# Page05_DDR4L_eMMC.net
KiCad netlist of a schematic drawn in Altium Designer
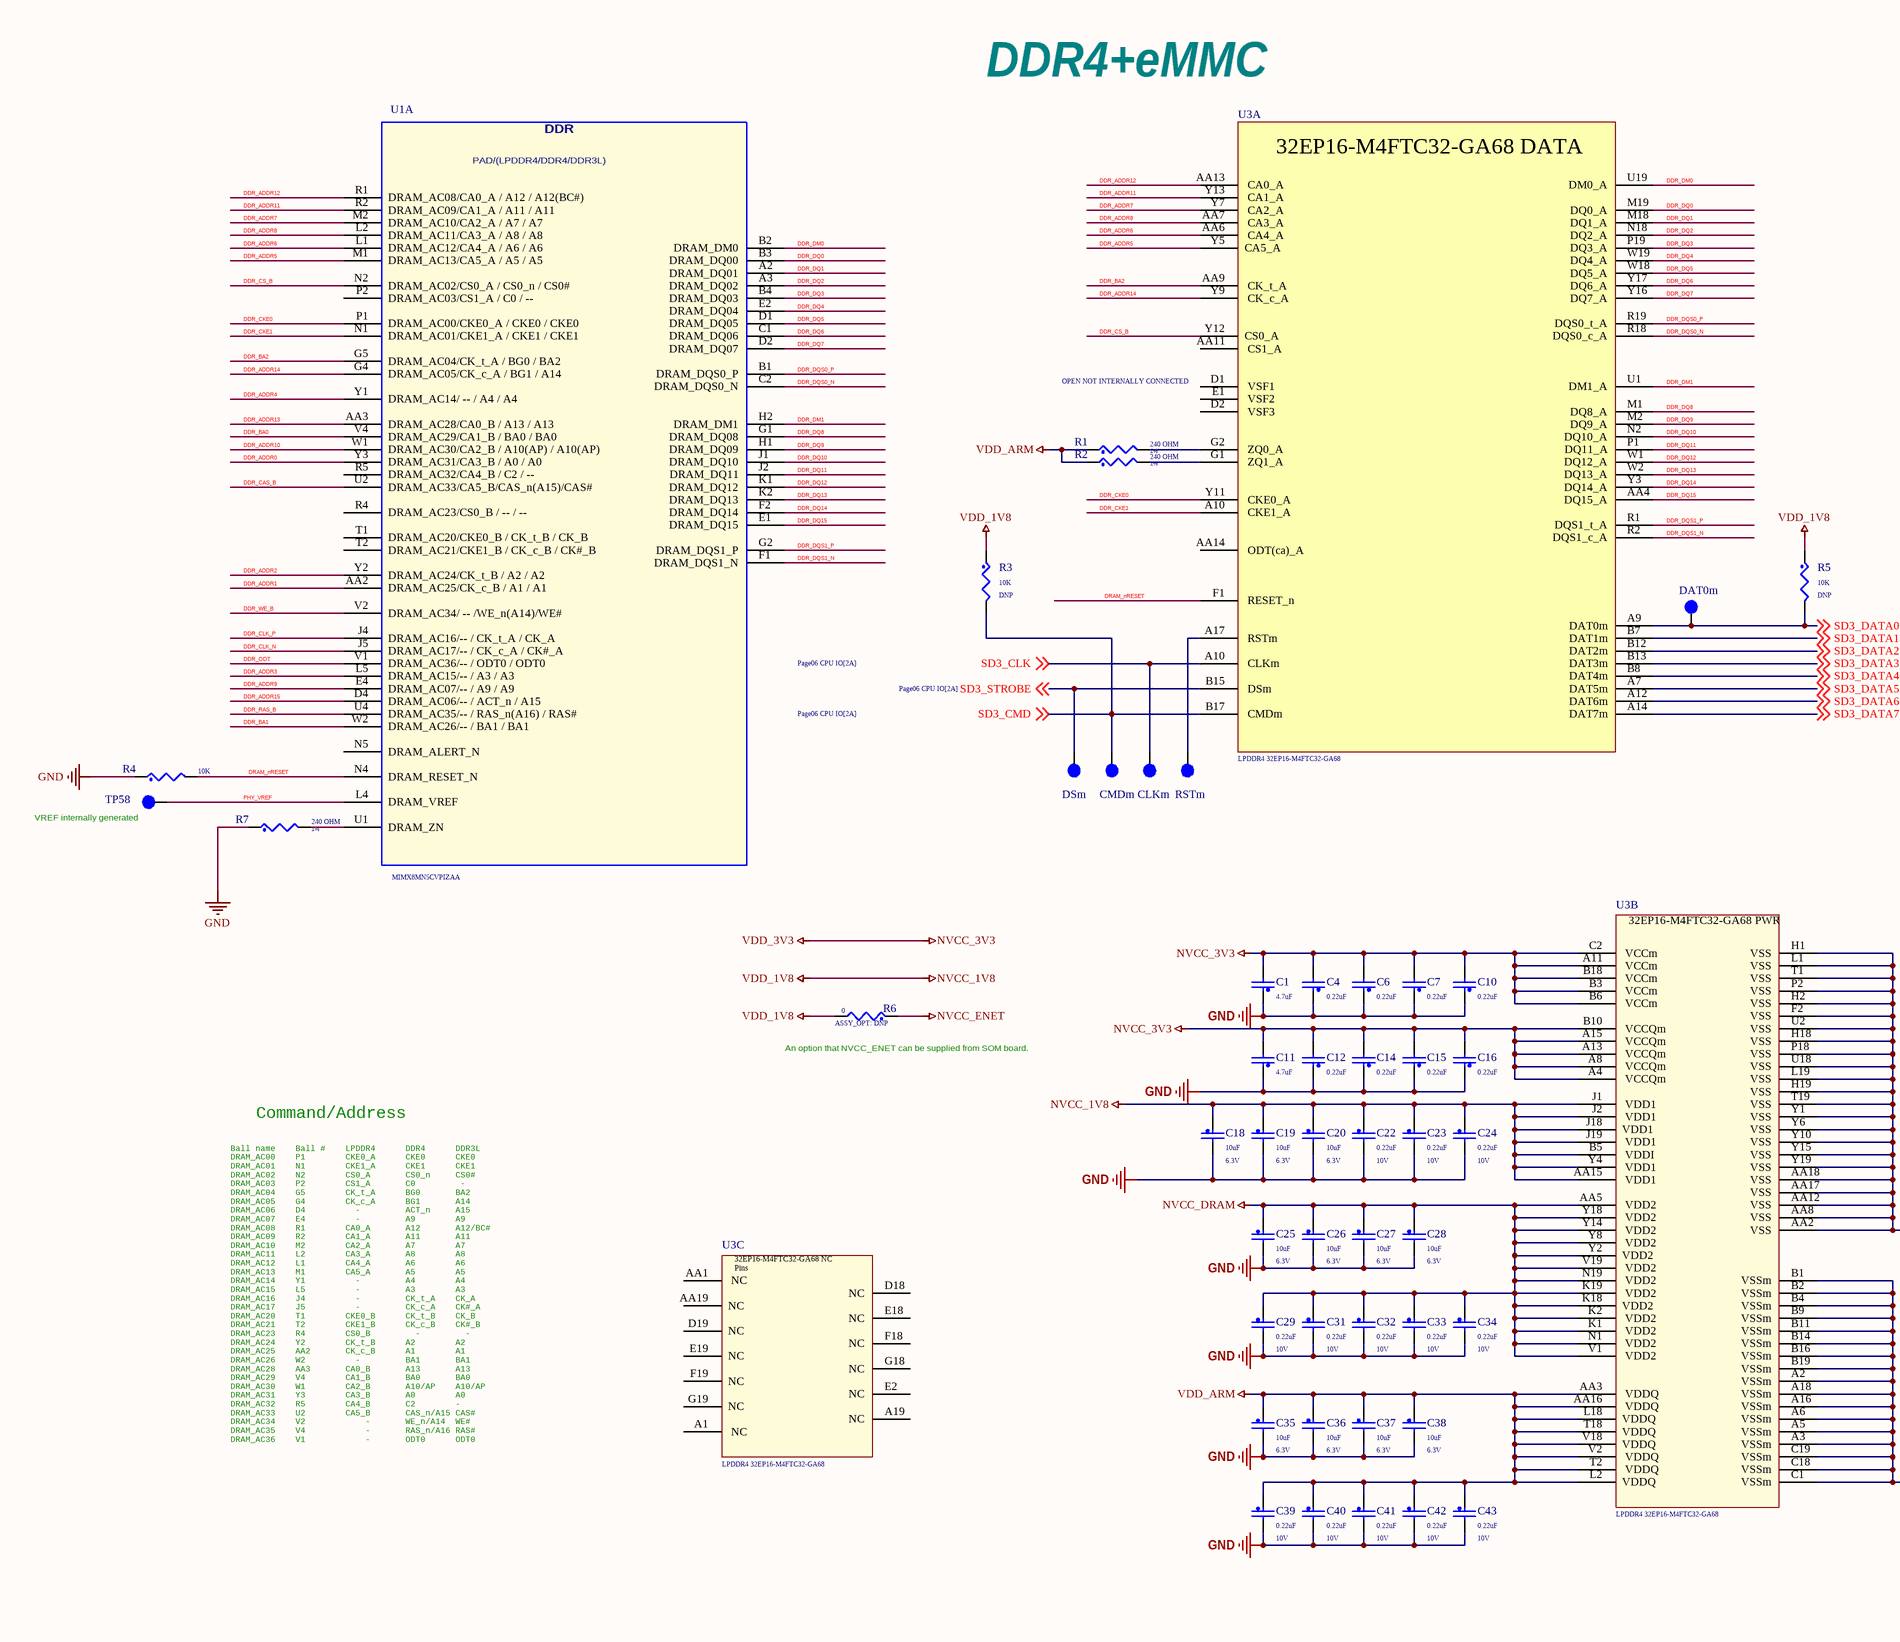
[diagram p0: Page05 DDR4L+eMMC.SchDoc, left]
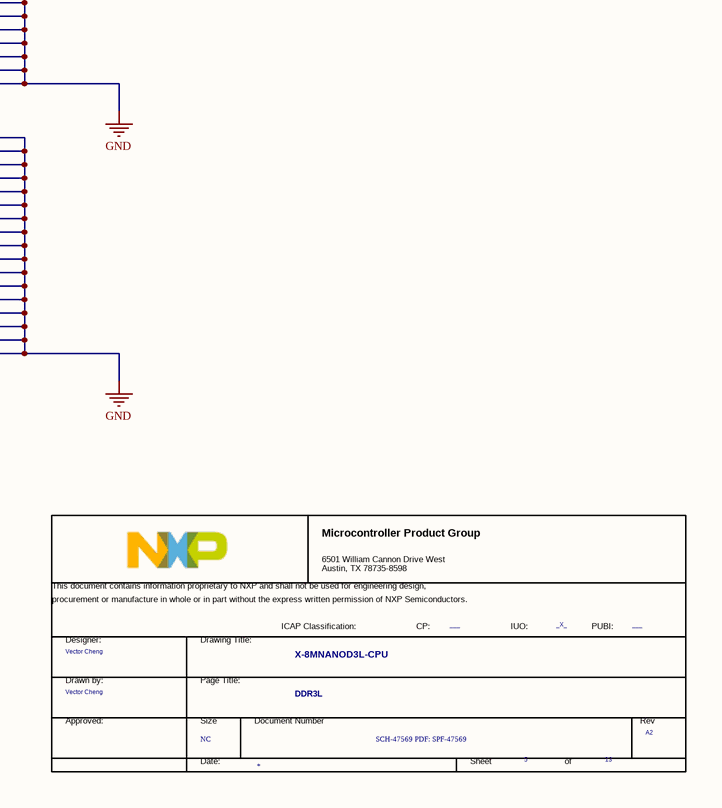
[diagram p1: Page05 DDR4L+eMMC.SchDoc, right]

(export (version "E")
  (design (tool "Eeschema 10.0.6"))
  (components
    (comp (ref "C1") (value "4.7uF") (footprint "0402_CC - C") (libsource (lib "AA_iMX8_M_") (part "CAP_NP")))
    (comp (ref "C4")
      (value "0.22uF")
      (footprint "0201_CC - C")
      (libsource (lib "AA_iMX8_M_") (part "CAP_NP"))
    )
    (comp (ref "C6")
      (value "0.22uF")
      (footprint "0201_CC - C")
      (libsource (lib "AA_iMX8_M_") (part "CAP_NP"))
    )
    (comp (ref "C7")
      (value "0.22uF")
      (footprint "0201_CC - C")
      (libsource (lib "AA_iMX8_M_") (part "CAP_NP"))
    )
    (comp (ref "C10")
      (value "0.22uF")
      (footprint "0201_CC - C")
      (libsource (lib "AA_iMX8_M_") (part "CAP_NP"))
    )
    (comp (ref "C11")
      (value "4.7uF")
      (footprint "0402_CC - C")
      (libsource (lib "AA_iMX8_M_") (part "CAP_NP"))
    )
    (comp (ref "C12")
      (value "0.22uF")
      (footprint "0201_CC - C")
      (libsource (lib "AA_iMX8_M_") (part "CAP_NP"))
    )
    (comp (ref "C14")
      (value "0.22uF")
      (footprint "0201_CC - C")
      (libsource (lib "AA_iMX8_M_") (part "CAP_NP"))
    )
    (comp (ref "C15")
      (value "0.22uF")
      (footprint "0201_CC - C")
      (libsource (lib "AA_iMX8_M_") (part "CAP_NP"))
    )
    (comp (ref "C16")
      (value "0.22uF")
      (footprint "0201_CC - C")
      (libsource (lib "AA_iMX8_M_") (part "CAP_NP"))
    )
    (comp (ref "C18")
      (value "10uF")
      (footprint "0402_CC - C")
      (fields (field (name "VOLTAGE") "6.3V"))
      (libsource (lib "AA_iMX8_M_") (part "CAP_NP"))
    )
    (comp (ref "C19")
      (value "10uF")
      (footprint "0402_CC - C")
      (fields (field (name "VOLTAGE") "6.3V"))
      (libsource (lib "AA_iMX8_M_") (part "CAP_NP"))
    )
    (comp (ref "C20")
      (value "10uF")
      (footprint "0402_CC - C")
      (fields (field (name "VOLTAGE") "6.3V"))
      (libsource (lib "AA_iMX8_M_") (part "CAP_NP"))
    )
    (comp (ref "C22")
      (value "0.22uF")
      (footprint "0201_CC - C")
      (fields (field (name "VOLTAGE") "10V"))
      (libsource (lib "AA_iMX8_M_") (part "CAP_NP"))
    )
    (comp (ref "C23")
      (value "0.22uF")
      (footprint "0201_CC - C")
      (fields (field (name "VOLTAGE") "10V"))
      (libsource (lib "AA_iMX8_M_") (part "CAP_NP"))
    )
    (comp (ref "C24")
      (value "0.22uF")
      (footprint "0201_CC - C")
      (fields (field (name "VOLTAGE") "10V"))
      (libsource (lib "AA_iMX8_M_") (part "CAP_NP"))
    )
    (comp (ref "C25")
      (value "10uF")
      (footprint "0402_CC - C")
      (fields (field (name "VOLTAGE") "6.3V"))
      (libsource (lib "AA_iMX8_M_") (part "CAP_NP"))
    )
    (comp (ref "C26")
      (value "10uF")
      (footprint "0402_CC - C")
      (fields (field (name "VOLTAGE") "6.3V"))
      (libsource (lib "AA_iMX8_M_") (part "CAP_NP"))
    )
    (comp (ref "C27")
      (value "10uF")
      (footprint "0402_CC - C")
      (fields (field (name "VOLTAGE") "6.3V"))
      (libsource (lib "AA_iMX8_M_") (part "CAP_NP"))
    )
    (comp (ref "C28")
      (value "10uF")
      (footprint "0402_CC - C")
      (fields (field (name "VOLTAGE") "6.3V"))
      (libsource (lib "AA_iMX8_M_") (part "CAP_NP"))
    )
    (comp (ref "C29")
      (value "0.22uF")
      (footprint "0201_CC - C")
      (fields (field (name "VOLTAGE") "10V"))
      (libsource (lib "AA_iMX8_M_") (part "CAP_NP"))
    )
    (comp (ref "C31")
      (value "0.22uF")
      (footprint "0201_CC - C")
      (fields (field (name "VOLTAGE") "10V"))
      (libsource (lib "AA_iMX8_M_") (part "CAP_NP"))
    )
    (comp (ref "C32")
      (value "0.22uF")
      (footprint "0201_CC - C")
      (fields (field (name "VOLTAGE") "10V"))
      (libsource (lib "AA_iMX8_M_") (part "CAP_NP"))
    )
    (comp (ref "C33")
      (value "0.22uF")
      (footprint "0201_CC - C")
      (fields (field (name "VOLTAGE") "10V"))
      (libsource (lib "AA_iMX8_M_") (part "CAP_NP"))
    )
    (comp (ref "C34")
      (value "0.22uF")
      (footprint "0201_CC - C")
      (fields (field (name "VOLTAGE") "10V"))
      (libsource (lib "AA_iMX8_M_") (part "CAP_NP"))
    )
    (comp (ref "C35")
      (value "10uF")
      (footprint "0402_CC - C")
      (fields (field (name "VOLTAGE") "6.3V"))
      (libsource (lib "AA_iMX8_M_") (part "CAP_NP"))
    )
    (comp (ref "C36")
      (value "10uF")
      (footprint "0402_CC - C")
      (fields (field (name "VOLTAGE") "6.3V"))
      (libsource (lib "AA_iMX8_M_") (part "CAP_NP"))
    )
    (comp (ref "C37")
      (value "10uF")
      (footprint "0402_CC - C")
      (fields (field (name "VOLTAGE") "6.3V"))
      (libsource (lib "AA_iMX8_M_") (part "CAP_NP"))
    )
    (comp (ref "C38")
      (value "10uF")
      (footprint "0402_CC - C")
      (fields (field (name "VOLTAGE") "6.3V"))
      (libsource (lib "AA_iMX8_M_") (part "CAP_NP"))
    )
    (comp (ref "C39")
      (value "0.22uF")
      (footprint "0201_CC - C")
      (fields (field (name "VOLTAGE") "10V"))
      (libsource (lib "AA_iMX8_M_") (part "CAP_NP"))
    )
    (comp (ref "C40")
      (value "0.22uF")
      (footprint "0201_CC - C")
      (fields (field (name "VOLTAGE") "10V"))
      (libsource (lib "AA_iMX8_M_") (part "CAP_NP"))
    )
    (comp (ref "C41")
      (value "0.22uF")
      (footprint "0201_CC - C")
      (fields (field (name "VOLTAGE") "10V"))
      (libsource (lib "AA_iMX8_M_") (part "CAP_NP"))
    )
    (comp (ref "C42")
      (value "0.22uF")
      (footprint "0201_CC - C")
      (fields (field (name "VOLTAGE") "10V"))
      (libsource (lib "AA_iMX8_M_") (part "CAP_NP"))
    )
    (comp (ref "C43")
      (value "0.22uF")
      (footprint "0201_CC - C")
      (fields (field (name "VOLTAGE") "10V"))
      (libsource (lib "AA_iMX8_M_") (part "CAP_NP"))
    )
    (comp (ref "CLKm")
      (value "tpad_020")
      (footprint "Test Pin")
      (description "TEST POINT PAD 0.5MM DIA SMT, NO PART TO ORDER")
      (libsource (lib "*") (part "TESTLOOP"))
    )
    (comp (ref "CMDm")
      (value "TPAD_015")
      (footprint "Test Pin")
      (description "TEST POINT PAD 15MIL DIA SMT, NO PART TO ORDER")
      (libsource (lib "*") (part "TESTLOOP"))
    )
    (comp (ref "DAT0m")
      (value "tpad_020")
      (footprint "Test Pin")
      (description "TEST POINT PAD 0.5MM DIA SMT, NO PART TO ORDER")
      (libsource (lib "*") (part "TESTLOOP"))
    )
    (comp (ref "DSm")
      (value "TPAD_015")
      (footprint "Test Pin")
      (description "TEST POINT PAD 15MIL DIA SMT, NO PART TO ORDER")
      (libsource (lib "*") (part "TESTLOOP"))
    )
    (comp (ref "R1")
      (value "240 OHM")
      (footprint "0201_RES")
      (description "RES MF 240 OHM 1/20W 1% 0201")
      (fields (field (name "VOLTAGE") "25V") (field (name "TOLERANCE") "1%"))
      (libsource (lib "*") (part "RES"))
    )
    (comp (ref "R2")
      (value "240 OHM")
      (footprint "0201_RES")
      (description "RES MF 240 OHM 1/20W 1% 0201")
      (fields (field (name "VOLTAGE") "25V") (field (name "TOLERANCE") "1%"))
      (libsource (lib "*") (part "RES"))
    )
    (comp (ref "R3")
      (value "10K")
      (footprint "0201_RES")
      (description "RES MF 10K 1/20W 5% 0201")
      (fields (field (name "ASSY_OPT") "DNP") (field (name "TOLERANCE") "5%"))
      (libsource (lib "*") (part "RES"))
    )
    (comp (ref "R4")
      (value "10K")
      (footprint "0201_RES")
      (description "RES MF 10K 1/20W 5% 0201")
      (fields (field (name "TOLERANCE") "5%"))
      (libsource (lib "*") (part "RES"))
    )
    (comp (ref "R5")
      (value "10K")
      (footprint "0201_RES")
      (description "RES MF 10K 1/20W 5% 0201")
      (fields (field (name "ASSY_OPT") "DNP") (field (name "TOLERANCE") "5%"))
      (libsource (lib "*") (part "RES"))
    )
    (comp (ref "R6")
      (value "0")
      (footprint "0402_CC_RES")
      (description "RES MF ZERO OHM 1/16W 5% 0402")
      (fields
        (field (name "ASSY_OPT") "DNP")
        (field (name "TOLERANCE") "5%")
        (field (name "VOLTAGE") "1/16W")
      )
      (libsource (lib "*") (part "RES"))
    )
    (comp (ref "R7")
      (value "240 OHM")
      (footprint "0201_RES")
      (description "RES MF 240 OHM 1/20W 1% 0201")
      (fields (field (name "VOLTAGE") "25V") (field (name "TOLERANCE") "1%"))
      (libsource (lib "*") (part "RES"))
    )
    (comp (ref "RSTm")
      (value "tpad_020")
      (footprint "Test Pin")
      (description "TEST POINT PAD 0.5MM DIA SMT, NO PART TO ORDER")
      (libsource (lib "*") (part "TESTLOOP"))
    )
    (comp (ref "TP58")
      (value "tpad_020")
      (footprint "Test Pin")
      (description "TEST POINT PAD 0.5MM DIA SMT, NO PART TO ORDER")
      (libsource (lib "*") (part "TESTLOOP"))
    )
    (comp (ref "U1")
      (value "MIMX8MN5CVPIZAA")
      (footprint "BGA306C50P21X21_1100X1100X101")
      (description "IC CPU QUAD CORTEX A53+M7 1.4GHZ -- BGA306")
      (libsource (lib "*") (part "MIMX8MN"))
    )
    (comp (ref "U3")
      (value "LPDDR4 32EP16-M4FTC32-GA68")
      (footprint "FBGA144C40P19X21_800X950X80")
      (libsource (lib "Altium starter project NANO") (part "LPDDR4 32EP16-M4FTC32-GA68"))
    )
  )
  (nets
    (net (code "1") (name "/DDR_ADDR0") (class "Default")
      (node (ref "U1") (pin "Y3") (pinfunction "DRAM_AC31/CA3_B_/_A0_/_A0_Y3") (pintype "passive"))
    )
    (net (code "2") (name "/DDR_ADDR1") (class "Default")
      (node (ref "U1") (pin "AA2") (pinfunction "DRAM_AC25/CK_c_B_/_A1_/_A1_AA2") (pintype "passive"))
    )
    (net (code "3") (name "/DDR_ADDR2") (class "Default")
      (node (ref "U1") (pin "Y2") (pinfunction "DRAM_AC24/CK_t_B_/_A2_/_A2_Y2") (pintype "passive"))
    )
    (net (code "4") (name "/DDR_ADDR3") (class "Default")
      (node (ref "U1") (pin "L5") (pinfunction "DRAM_AC15/--_/_A3_/_A3_L5") (pintype "passive"))
    )
    (net (code "5") (name "/DDR_ADDR4") (class "Default")
      (node (ref "U1") (pin "Y1") (pinfunction "DRAM_AC14/_--_/_A4_/_A4_Y1") (pintype "passive"))
    )
    (net (code "6") (name "/DDR_ADDR5") (class "Default")
      (node (ref "U1") (pin "M1") (pinfunction "DRAM_AC13/CA5_A_/_A5_/_A5_M1") (pintype "passive"))
      (node (ref "U3") (pin "Y5") (pinfunction "CA5_A_Y5") (pintype "passive"))
    )
    (net (code "7") (name "/DDR_ADDR6") (class "Default")
      (node (ref "U1") (pin "L1") (pinfunction "DRAM_AC12/CA4_A_/_A6_/_A6_L1") (pintype "passive"))
      (node (ref "U3") (pin "AA6") (pinfunction "_CA4_A_AA6") (pintype "passive"))
    )
    (net (code "8") (name "/DDR_ADDR7") (class "Default")
      (node (ref "U1") (pin "M2") (pinfunction "DRAM_AC10/CA2_A_/_A7_/_A7_M2") (pintype "passive"))
      (node (ref "U3") (pin "Y7") (pinfunction "_CA2_A_Y7") (pintype "passive"))
    )
    (net (code "9") (name "/DDR_ADDR8") (class "Default")
      (node (ref "U1") (pin "L2") (pinfunction "DRAM_AC11/CA3_A_/_A8_/_A8_L2") (pintype "passive"))
      (node (ref "U3") (pin "AA7") (pinfunction "_CA3_A_AA7") (pintype "passive"))
    )
    (net (code "10") (name "/DDR_ADDR9") (class "Default")
      (node (ref "U1") (pin "E4") (pinfunction "DRAM_AC07/--_/_A9_/_A9_E4") (pintype "passive"))
    )
    (net (code "11") (name "/DDR_ADDR10") (class "Default")
      (node (ref "U1") (pin "W1") (pinfunction "DRAM_AC30/CA2_B_/_A10(AP)_/_A10(AP)_W1") (pintype "passive"))
    )
    (net (code "12") (name "/DDR_ADDR11") (class "Default")
      (node (ref "U1") (pin "R2") (pinfunction "DRAM_AC09/CA1_A_/_A11_/_A11_R2") (pintype "passive"))
      (node (ref "U3") (pin "Y13") (pinfunction "_CA1_A_Y13") (pintype "passive"))
    )
    (net (code "13") (name "/DDR_ADDR12") (class "Default")
      (node (ref "U1") (pin "R1") (pinfunction "DRAM_AC08/CA0_A_/_A12_/_A12(BC#)_R1") (pintype "passive"))
      (node (ref "U3") (pin "AA13") (pinfunction "_CA0_A_AA13") (pintype "passive"))
    )
    (net (code "14") (name "/DDR_ADDR13") (class "Default")
      (node (ref "U1") (pin "AA3") (pinfunction "DRAM_AC28/CA0_B_/_A13_/_A13_AA3") (pintype "passive"))
    )
    (net (code "15") (name "/DDR_ADDR14") (class "Default")
      (node (ref "U1") (pin "G4") (pinfunction "DRAM_AC05/CK_c_A_/_BG1_/_A14_G4") (pintype "passive"))
      (node (ref "U3") (pin "Y9") (pinfunction "_CK_c_A_Y9") (pintype "passive"))
    )
    (net (code "16") (name "/DDR_ADDR15") (class "Default")
      (node (ref "U1") (pin "D4") (pinfunction "DRAM_AC06/--_/_ACT_n_/_A15_D4") (pintype "passive"))
    )
    (net (code "17") (name "/DDR_BA0") (class "Default")
      (node (ref "U1") (pin "V4") (pinfunction "DRAM_AC29/CA1_B_/_BA0_/_BA0_V4") (pintype "passive"))
    )
    (net (code "18") (name "/DDR_BA1") (class "Default")
      (node (ref "U1") (pin "W2") (pinfunction "DRAM_AC26/--_/_BA1_/_BA1_W2") (pintype "passive"))
    )
    (net (code "19") (name "/DDR_BA2") (class "Default")
      (node (ref "U1") (pin "G5") (pinfunction "DRAM_AC04/CK_t_A_/_BG0_/_BA2_G5") (pintype "passive"))
      (node (ref "U3") (pin "AA9") (pinfunction "_CK_t_A_AA9") (pintype "passive"))
    )
    (net (code "20") (name "/DDR_CAS_B") (class "Default")
      (node (ref "U1") (pin "U2") (pinfunction "DRAM_AC33/CA5_B/CAS_n(A15)/CAS#_U2") (pintype "passive"))
    )
    (net (code "21") (name "/DDR_CKE0") (class "Default")
      (node (ref "U1") (pin "P1") (pinfunction "DRAM_AC00/CKE0_A_/_CKE0_/_CKE0_P1") (pintype "passive"))
      (node (ref "U3") (pin "Y11") (pinfunction "_CKE0_A_Y11") (pintype "passive"))
    )
    (net (code "22") (name "/DDR_CKE1") (class "Default")
      (node (ref "U1") (pin "N1") (pinfunction "DRAM_AC01/CKE1_A_/_CKE1_/_CKE1_N1") (pintype "passive"))
      (node (ref "U3") (pin "A10") (pinfunction "_CKE1_A_A10") (pintype "passive"))
    )
    (net (code "23") (name "/DDR_CLK_N") (class "Default")
      (node (ref "U1") (pin "J5") (pinfunction "DRAM_AC17/--_/_CK_c_A_/_CK#_A_J5") (pintype "passive"))
    )
    (net (code "24") (name "/DDR_CLK_P") (class "Default")
      (node (ref "U1") (pin "J4") (pinfunction "DRAM_AC16/--_/_CK_t_A_/_CK_A_J4") (pintype "passive"))
    )
    (net (code "25") (name "/DDR_CS_B") (class "Default")
      (node (ref "U1") (pin "N2") (pinfunction "DRAM_AC02/CS0_A_/_CS0_n_/_CS0#_N2") (pintype "passive"))
      (node (ref "U3") (pin "Y12") (pinfunction "CS0_A_Y12") (pintype "passive"))
    )
    (net (code "26") (name "/DDR_DM0") (class "Default")
      (node (ref "U1") (pin "B2") (pinfunction "DRAM_DM0_B2") (pintype "passive"))
      (node (ref "U3") (pin "U19") (pinfunction "_DM0_A_U19") (pintype "passive"))
    )
    (net (code "27") (name "/DDR_DM1") (class "Default")
      (node (ref "U1") (pin "H2") (pinfunction "DRAM_DM1_H2") (pintype "passive"))
      (node (ref "U3") (pin "U1") (pinfunction "_DM1_A_U1") (pintype "passive"))
    )
    (net (code "28") (name "/DDR_DQ0") (class "Default")
      (node (ref "U1") (pin "B3") (pinfunction "DRAM_DQ00_B3") (pintype "passive"))
      (node (ref "U3") (pin "M19") (pinfunction "_DQ0_A_M19") (pintype "passive"))
    )
    (net (code "29") (name "/DDR_DQ1") (class "Default")
      (node (ref "U1") (pin "A2") (pinfunction "DRAM_DQ01_A2") (pintype "passive"))
      (node (ref "U3") (pin "M18") (pinfunction "DQ1_A_M18") (pintype "passive"))
    )
    (net (code "30") (name "/DDR_DQ2") (class "Default")
      (node (ref "U1") (pin "A3") (pinfunction "DRAM_DQ02_A3") (pintype "passive"))
      (node (ref "U3") (pin "N18") (pinfunction "DQ2_A_N18") (pintype "passive"))
    )
    (net (code "31") (name "/DDR_DQ3") (class "Default")
      (node (ref "U1") (pin "B4") (pinfunction "DRAM_DQ03_B4") (pintype "passive"))
      (node (ref "U3") (pin "P19") (pinfunction "DQ3_A_P19") (pintype "passive"))
    )
    (net (code "32") (name "/DDR_DQ4") (class "Default")
      (node (ref "U1") (pin "E2") (pinfunction "DRAM_DQ04_E2") (pintype "passive"))
      (node (ref "U3") (pin "W19") (pinfunction "_DQ4_A_W19") (pintype "passive"))
    )
    (net (code "33") (name "/DDR_DQ5") (class "Default")
      (node (ref "U1") (pin "D1") (pinfunction "DRAM_DQ05_D1") (pintype "passive"))
      (node (ref "U3") (pin "W18") (pinfunction "DQ5_A_W18") (pintype "passive"))
    )
    (net (code "34") (name "/DDR_DQ6") (class "Default")
      (node (ref "U1") (pin "C1") (pinfunction "DRAM_DQ06_C1") (pintype "passive"))
      (node (ref "U3") (pin "Y17") (pinfunction "_DQ6_A_Y17") (pintype "passive"))
    )
    (net (code "35") (name "/DDR_DQ7") (class "Default")
      (node (ref "U1") (pin "D2") (pinfunction "DRAM_DQ07_D2") (pintype "passive"))
      (node (ref "U3") (pin "Y16") (pinfunction "_DQ7_A_Y16") (pintype "passive"))
    )
    (net (code "36") (name "/DDR_DQ8") (class "Default")
      (node (ref "U1") (pin "G1") (pinfunction "DRAM_DQ08_G1") (pintype "passive"))
      (node (ref "U3") (pin "M1") (pinfunction "_DQ8_A_M1") (pintype "passive"))
    )
    (net (code "37") (name "/DDR_DQ9") (class "Default")
      (node (ref "U1") (pin "H1") (pinfunction "DRAM_DQ09_H1") (pintype "passive"))
      (node (ref "U3") (pin "M2") (pinfunction "_DQ9_A_M2") (pintype "passive"))
    )
    (net (code "38") (name "/DDR_DQ10") (class "Default")
      (node (ref "U1") (pin "J1") (pinfunction "DRAM_DQ10_J1") (pintype "passive"))
      (node (ref "U3") (pin "N2") (pinfunction "_DQ10_A_N2") (pintype "passive"))
    )
    (net (code "39") (name "/DDR_DQ11") (class "Default")
      (node (ref "U1") (pin "J2") (pinfunction "DRAM_DQ11_J2") (pintype "passive"))
      (node (ref "U3") (pin "P1") (pinfunction "_DQ11_A_P1") (pintype "passive"))
    )
    (net (code "40") (name "/DDR_DQ12") (class "Default")
      (node (ref "U1") (pin "K1") (pinfunction "DRAM_DQ12_K1") (pintype "passive"))
      (node (ref "U3") (pin "W1") (pinfunction "_DQ12_A_W1") (pintype "passive"))
    )
    (net (code "41") (name "/DDR_DQ13") (class "Default")
      (node (ref "U1") (pin "K2") (pinfunction "DRAM_DQ13_K2") (pintype "passive"))
      (node (ref "U3") (pin "W2") (pinfunction "_DQ13_A_W2") (pintype "passive"))
    )
    (net (code "42") (name "/DDR_DQ14") (class "Default")
      (node (ref "U1") (pin "F2") (pinfunction "DRAM_DQ14_F2") (pintype "passive"))
      (node (ref "U3") (pin "Y3") (pinfunction "_DQ14_A_Y3") (pintype "passive"))
    )
    (net (code "43") (name "/DDR_DQ15") (class "Default")
      (node (ref "U1") (pin "E1") (pinfunction "DRAM_DQ15_E1") (pintype "passive"))
      (node (ref "U3") (pin "AA4") (pinfunction "_DQ15_A_AA4") (pintype "passive"))
    )
    (net (code "44") (name "/DDR_DQS0_N") (class "Default")
      (node (ref "U1") (pin "C2") (pinfunction "DRAM_DQS0_N_C2") (pintype "passive"))
      (node (ref "U3") (pin "R18") (pinfunction "DQS0_c_A_R18") (pintype "passive"))
    )
    (net (code "45") (name "/DDR_DQS0_P") (class "Default")
      (node (ref "U1") (pin "B1") (pinfunction "DRAM_DQS0_P_B1") (pintype "passive"))
      (node (ref "U3") (pin "R19") (pinfunction "_DQS0_t_A_R19") (pintype "passive"))
    )
    (net (code "46") (name "/DDR_DQS1_N") (class "Default")
      (node (ref "U1") (pin "F1") (pinfunction "DRAM_DQS1_N_F1") (pintype "passive"))
      (node (ref "U3") (pin "R2") (pinfunction "_DQS1_c_A_R2") (pintype "passive"))
    )
    (net (code "47") (name "/DDR_DQS1_P") (class "Default")
      (node (ref "U1") (pin "G2") (pinfunction "DRAM_DQS1_P_G2") (pintype "passive"))
      (node (ref "U3") (pin "R1") (pinfunction "_DQS1_t_A_R1") (pintype "passive"))
    )
    (net (code "48") (name "/DDR_ODT") (class "Default")
      (node (ref "U1") (pin "V1") (pinfunction "DRAM_AC36/--_/_ODT0_/_ODT0_V1") (pintype "passive"))
    )
    (net (code "49") (name "/DDR_RAS_B") (class "Default")
      (node (ref "U1") (pin "U4") (pinfunction "DRAM_AC35/--_/_RAS_n(A16)_/_RAS#_U4") (pintype "passive"))
    )
    (net (code "50") (name "/DDR_WE_B") (class "Default")
      (node (ref "U1") (pin "V2") (pinfunction "DRAM_AC34/_--_/WE_n(A14)/WE#_V2") (pintype "passive"))
    )
    (net (code "51") (name "/DRAM_nRESET") (class "Default")
      (node (ref "R4") (pin "2") (pinfunction "2_2") (pintype "passive"))
      (node (ref "U1") (pin "N4") (pinfunction "DRAM_RESET_N_N4") (pintype "passive"))
      (node (ref "U3") (pin "F1") (pinfunction "_RESET_n_F1") (pintype "passive"))
    )
    (net (code "52") (name "/PHY_VREF") (class "Default")
      (node (ref "TP58") (pin "1") (pinfunction "Pin1_1") (pintype "passive"))
      (node (ref "U1") (pin "L4") (pinfunction "DRAM_VREF_L4") (pintype "passive"))
    )
    (net (code "53") (name "GND") (class "Default")
      (node (ref "C1") (pin "1") (pinfunction "1_1") (pintype "passive"))
      (node (ref "C10") (pin "1") (pinfunction "1_1") (pintype "passive"))
      (node (ref "C11") (pin "1") (pinfunction "1_1") (pintype "passive"))
      (node (ref "C12") (pin "1") (pinfunction "1_1") (pintype "passive"))
      (node (ref "C14") (pin "1") (pinfunction "1_1") (pintype "passive"))
      (node (ref "C15") (pin "1") (pinfunction "1_1") (pintype "passive"))
      (node (ref "C16") (pin "1") (pinfunction "1_1") (pintype "passive"))
      (node (ref "C18") (pin "2") (pinfunction "2_2") (pintype "passive"))
      (node (ref "C19") (pin "2") (pinfunction "2_2") (pintype "passive"))
      (node (ref "C20") (pin "2") (pinfunction "2_2") (pintype "passive"))
      (node (ref "C22") (pin "2") (pinfunction "2_2") (pintype "passive"))
      (node (ref "C23") (pin "2") (pinfunction "2_2") (pintype "passive"))
      (node (ref "C24") (pin "2") (pinfunction "2_2") (pintype "passive"))
      (node (ref "C25") (pin "2") (pinfunction "2_2") (pintype "passive"))
      (node (ref "C26") (pin "2") (pinfunction "2_2") (pintype "passive"))
      (node (ref "C27") (pin "2") (pinfunction "2_2") (pintype "passive"))
      (node (ref "C28") (pin "2") (pinfunction "2_2") (pintype "passive"))
      (node (ref "C29") (pin "2") (pinfunction "2_2") (pintype "passive"))
      (node (ref "C31") (pin "2") (pinfunction "2_2") (pintype "passive"))
      (node (ref "C32") (pin "2") (pinfunction "2_2") (pintype "passive"))
      (node (ref "C33") (pin "2") (pinfunction "2_2") (pintype "passive"))
      (node (ref "C34") (pin "2") (pinfunction "2_2") (pintype "passive"))
      (node (ref "C35") (pin "2") (pinfunction "2_2") (pintype "passive"))
      (node (ref "C36") (pin "2") (pinfunction "2_2") (pintype "passive"))
      (node (ref "C37") (pin "2") (pinfunction "2_2") (pintype "passive"))
      (node (ref "C38") (pin "2") (pinfunction "2_2") (pintype "passive"))
      (node (ref "C39") (pin "2") (pinfunction "2_2") (pintype "passive"))
      (node (ref "C4") (pin "1") (pinfunction "1_1") (pintype "passive"))
      (node (ref "C40") (pin "2") (pinfunction "2_2") (pintype "passive"))
      (node (ref "C41") (pin "2") (pinfunction "2_2") (pintype "passive"))
      (node (ref "C42") (pin "2") (pinfunction "2_2") (pintype "passive"))
      (node (ref "C43") (pin "2") (pinfunction "2_2") (pintype "passive"))
      (node (ref "C6") (pin "1") (pinfunction "1_1") (pintype "passive"))
      (node (ref "C7") (pin "1") (pinfunction "1_1") (pintype "passive"))
      (node (ref "R4") (pin "1") (pinfunction "1_1") (pintype "passive"))
      (node (ref "R7") (pin "1") (pinfunction "1_1") (pintype "passive"))
      (node (ref "U3") (pin "A16") (pinfunction "_VSSm_A16") (pintype "power_in"))
      (node (ref "U3") (pin "A18") (pinfunction "_VSSm_A18") (pintype "power_in"))
      (node (ref "U3") (pin "A2") (pinfunction "_VSSm_A2") (pintype "power_in"))
      (node (ref "U3") (pin "A3") (pinfunction "VSSm_A3") (pintype "power_in"))
      (node (ref "U3") (pin "A5") (pinfunction "_VSSm_A5") (pintype "power_in"))
      (node (ref "U3") (pin "A6") (pinfunction "_VSSm_A6") (pintype "power_in"))
      (node (ref "U3") (pin "AA12") (pinfunction "_VSS_AA12") (pintype "power_in"))
      (node (ref "U3") (pin "AA17") (pinfunction "_VSS_AA17") (pintype "power_in"))
      (node (ref "U3") (pin "AA18") (pinfunction "VSS_AA18") (pintype "power_in"))
      (node (ref "U3") (pin "AA2") (pinfunction "VSS_AA2") (pintype "power_in"))
      (node (ref "U3") (pin "AA8") (pinfunction "_VSS_AA8") (pintype "power_in"))
      (node (ref "U3") (pin "B1") (pinfunction "_VSSm_B1") (pintype "power_in"))
      (node (ref "U3") (pin "B11") (pinfunction "_VSSm_B11") (pintype "power_in"))
      (node (ref "U3") (pin "B14") (pinfunction "_VSSm_B14") (pintype "power_in"))
      (node (ref "U3") (pin "B16") (pinfunction "_VSSm_B16") (pintype "power_in"))
      (node (ref "U3") (pin "B19") (pinfunction "_VSSm_B19") (pintype "power_in"))
      (node (ref "U3") (pin "B2") (pinfunction "_VSSm_B2") (pintype "power_in"))
      (node (ref "U3") (pin "B4") (pinfunction "_VSSm_B4") (pintype "power_in"))
      (node (ref "U3") (pin "B9") (pinfunction "_VSSm_B9") (pintype "power_in"))
      (node (ref "U3") (pin "C1") (pinfunction "_VSSm_C1") (pintype "power_in"))
      (node (ref "U3") (pin "C18") (pinfunction "VSSm_C18") (pintype "power_in"))
      (node (ref "U3") (pin "C19") (pinfunction "_VSSm_C19") (pintype "power_in"))
      (node (ref "U3") (pin "F2") (pinfunction "_VSS_F2") (pintype "power_in"))
      (node (ref "U3") (pin "H1") (pinfunction "_VSS_H1") (pintype "power_in"))
      (node (ref "U3") (pin "H18") (pinfunction "VSS_H18") (pintype "power_in"))
      (node (ref "U3") (pin "H19") (pinfunction "VSS_H19") (pintype "power_in"))
      (node (ref "U3") (pin "H2") (pinfunction "VSS_H2") (pintype "power_in"))
      (node (ref "U3") (pin "L1") (pinfunction "_VSS_L1") (pintype "power_in"))
      (node (ref "U3") (pin "L19") (pinfunction "VSS_L19") (pintype "power_in"))
      (node (ref "U3") (pin "P18") (pinfunction "VSS_P18") (pintype "power_in"))
      (node (ref "U3") (pin "P2") (pinfunction "_VSS_P2") (pintype "power_in"))
      (node (ref "U3") (pin "T1") (pinfunction "_VSS_T1") (pintype "power_in"))
      (node (ref "U3") (pin "T19") (pinfunction "VSS_T19") (pintype "power_in"))
      (node (ref "U3") (pin "U18") (pinfunction "VSS_U18") (pintype "power_in"))
      (node (ref "U3") (pin "U2") (pinfunction "_VSS_U2") (pintype "power_in"))
      (node (ref "U3") (pin "Y1") (pinfunction "_VSS_Y1") (pintype "power_in"))
      (node (ref "U3") (pin "Y10") (pinfunction "_VSS_Y10") (pintype "power_in"))
      (node (ref "U3") (pin "Y15") (pinfunction "_VSS_Y15") (pintype "power_in"))
      (node (ref "U3") (pin "Y19") (pinfunction "VSS_Y19") (pintype "power_in"))
      (node (ref "U3") (pin "Y6") (pinfunction "_VSS_Y6") (pintype "power_in"))
    )
    (net (code "54") (name "NVCC_1V8") (class "Default")
      (node (ref "C18") (pin "1") (pinfunction "1_1") (pintype "passive"))
      (node (ref "C19") (pin "1") (pinfunction "1_1") (pintype "passive"))
      (node (ref "C20") (pin "1") (pinfunction "1_1") (pintype "passive"))
      (node (ref "C22") (pin "1") (pinfunction "1_1") (pintype "passive"))
      (node (ref "C23") (pin "1") (pinfunction "1_1") (pintype "passive"))
      (node (ref "C24") (pin "1") (pinfunction "1_1") (pintype "passive"))
      (node (ref "R3") (pin "1") (pinfunction "1_1") (pintype "passive"))
      (node (ref "R5") (pin "1") (pinfunction "1_1") (pintype "passive"))
      (node (ref "R6") (pin "2") (pinfunction "2_2") (pintype "passive"))
      (node (ref "U3") (pin "AA15") (pinfunction "_VDD1_AA15") (pintype "power_in"))
      (node (ref "U3") (pin "B5") (pinfunction "_VDDI_B5") (pintype "power_in"))
      (node (ref "U3") (pin "J1") (pinfunction "_VDD1_J1") (pintype "power_in"))
      (node (ref "U3") (pin "J18") (pinfunction "VDD1_J18") (pintype "power_in"))
      (node (ref "U3") (pin "J19") (pinfunction "_VDD1_J19") (pintype "power_in"))
      (node (ref "U3") (pin "J2") (pinfunction "_VDD1_J2") (pintype "power_in"))
      (node (ref "U3") (pin "Y4") (pinfunction "_VDD1_Y4") (pintype "power_in"))
    )
    (net (code "55") (name "NVCC_3V3") (class "Default")
      (node (ref "C1") (pin "2") (pinfunction "2_2") (pintype "passive"))
      (node (ref "C10") (pin "2") (pinfunction "2_2") (pintype "passive"))
      (node (ref "C11") (pin "2") (pinfunction "2_2") (pintype "passive"))
      (node (ref "C12") (pin "2") (pinfunction "2_2") (pintype "passive"))
      (node (ref "C14") (pin "2") (pinfunction "2_2") (pintype "passive"))
      (node (ref "C15") (pin "2") (pinfunction "2_2") (pintype "passive"))
      (node (ref "C16") (pin "2") (pinfunction "2_2") (pintype "passive"))
      (node (ref "C4") (pin "2") (pinfunction "2_2") (pintype "passive"))
      (node (ref "C6") (pin "2") (pinfunction "2_2") (pintype "passive"))
      (node (ref "C7") (pin "2") (pinfunction "2_2") (pintype "passive"))
      (node (ref "U3") (pin "A11") (pinfunction "_VCCm_A11") (pintype "power_in"))
      (node (ref "U3") (pin "A13") (pinfunction "_VCCQm_A13") (pintype "power_in"))
      (node (ref "U3") (pin "A15") (pinfunction "_VCCQm_A15") (pintype "power_in"))
      (node (ref "U3") (pin "A4") (pinfunction "_VCCQm_A4") (pintype "power_in"))
      (node (ref "U3") (pin "A8") (pinfunction "_VCCQm_A8") (pintype "power_in"))
      (node (ref "U3") (pin "B10") (pinfunction "_VCCQm_B10") (pintype "power_in"))
      (node (ref "U3") (pin "B18") (pinfunction "_VCCm_B18") (pintype "power_in"))
      (node (ref "U3") (pin "B3") (pinfunction "_VCCm_B3") (pintype "power_in"))
      (node (ref "U3") (pin "B6") (pinfunction "_VCCm_B6") (pintype "power_in"))
      (node (ref "U3") (pin "C2") (pinfunction "_VCCm_C2") (pintype "power_in"))
    )
    (net (code "56") (name "NVCC_DRAM") (class "Default")
      (node (ref "C25") (pin "1") (pinfunction "1_1") (pintype "passive"))
      (node (ref "C26") (pin "1") (pinfunction "1_1") (pintype "passive"))
      (node (ref "C27") (pin "1") (pinfunction "1_1") (pintype "passive"))
      (node (ref "C28") (pin "1") (pinfunction "1_1") (pintype "passive"))
      (node (ref "C29") (pin "1") (pinfunction "1_1") (pintype "passive"))
      (node (ref "C31") (pin "1") (pinfunction "1_1") (pintype "passive"))
      (node (ref "C32") (pin "1") (pinfunction "1_1") (pintype "passive"))
      (node (ref "C33") (pin "1") (pinfunction "1_1") (pintype "passive"))
      (node (ref "C34") (pin "1") (pinfunction "1_1") (pintype "passive"))
      (node (ref "U3") (pin "AA5") (pinfunction "_VDD2_AA5") (pintype "power_in"))
      (node (ref "U3") (pin "K1") (pinfunction "_VDD2_K1") (pintype "power_in"))
      (node (ref "U3") (pin "K18") (pinfunction "VDD2_K18") (pintype "power_in"))
      (node (ref "U3") (pin "K19") (pinfunction "_VDD2_K19") (pintype "power_in"))
      (node (ref "U3") (pin "K2") (pinfunction "_VDD2_K2") (pintype "power_in"))
      (node (ref "U3") (pin "N1") (pinfunction "_VDD2_N1") (pintype "power_in"))
      (node (ref "U3") (pin "N19") (pinfunction "_VDD2_N19") (pintype "power_in"))
      (node (ref "U3") (pin "V1") (pinfunction "_VDD2_V1") (pintype "power_in"))
      (node (ref "U3") (pin "V19") (pinfunction "_VDD2_V19") (pintype "power_in"))
      (node (ref "U3") (pin "Y14") (pinfunction "_VDD2_Y14") (pintype "power_in"))
      (node (ref "U3") (pin "Y18") (pinfunction "_VDD2_Y18") (pintype "power_in"))
      (node (ref "U3") (pin "Y2") (pinfunction "VDD2_Y2") (pintype "power_in"))
      (node (ref "U3") (pin "Y8") (pinfunction "_VDD2_Y8") (pintype "power_in"))
    )
    (net (code "57") (name "NVCC_ENET") (class "Default")
      (node (ref "R6") (pin "1") (pinfunction "1_1") (pintype "passive"))
    )
    (net (code "58") (name "Net-(RSTm-Pin1)") (class "Default")
      (node (ref "RSTm") (pin "1") (pinfunction "Pin1_1") (pintype "passive"))
      (node (ref "U3") (pin "A17") (pinfunction "_RSTm_A17") (pintype "passive"))
    )
    (net (code "59") (name "Net-(U1A-DRAM_ZN)") (class "Default")
      (node (ref "R7") (pin "2") (pinfunction "2_2") (pintype "passive"))
      (node (ref "U1") (pin "U1") (pinfunction "DRAM_ZN_U1") (pintype "passive"))
    )
    (net (code "60") (name "Net-(U3A-_ZQ0_A)") (class "Default")
      (node (ref "R1") (pin "2") (pinfunction "2_2") (pintype "passive"))
      (node (ref "U3") (pin "G2") (pinfunction "_ZQ0_A_G2") (pintype "passive"))
    )
    (net (code "61") (name "Net-(U3A-_ZQ1_A)") (class "Default")
      (node (ref "R2") (pin "2") (pinfunction "2_2") (pintype "passive"))
      (node (ref "U3") (pin "G1") (pinfunction "_ZQ1_A_G1") (pintype "passive"))
    )
    (net (code "62") (name "SD3_CLK") (class "Default")
      (node (ref "CLKm") (pin "1") (pinfunction "Pin1_1") (pintype "passive"))
      (node (ref "U3") (pin "A10") (pinfunction "_CLKm_A10") (pintype "passive"))
    )
    (net (code "63") (name "SD3_CMD") (class "Default")
      (node (ref "CMDm") (pin "1") (pinfunction "Pin1_1") (pintype "passive"))
      (node (ref "R3") (pin "2") (pinfunction "2_2") (pintype "passive"))
      (node (ref "U3") (pin "B17") (pinfunction "_CMDm_B17") (pintype "passive"))
    )
    (net (code "64") (name "SD3_DATA0") (class "Default")
      (node (ref "DAT0m") (pin "1") (pinfunction "Pin1_1") (pintype "passive"))
      (node (ref "R5") (pin "2") (pinfunction "2_2") (pintype "passive"))
      (node (ref "U3") (pin "A9") (pinfunction "_DAT0m_A9") (pintype "passive"))
    )
    (net (code "65") (name "SD3_DATA1") (class "Default")
      (node (ref "U3") (pin "B7") (pinfunction "DAT1m_B7") (pintype "passive"))
    )
    (net (code "66") (name "SD3_DATA2") (class "Default")
      (node (ref "U3") (pin "B12") (pinfunction "_DAT2m_B12") (pintype "passive"))
    )
    (net (code "67") (name "SD3_DATA3") (class "Default")
      (node (ref "U3") (pin "B13") (pinfunction "_DAT3m_B13") (pintype "passive"))
    )
    (net (code "68") (name "SD3_DATA4") (class "Default")
      (node (ref "U3") (pin "B8") (pinfunction "_DAT4m_B8") (pintype "passive"))
    )
    (net (code "69") (name "SD3_DATA5") (class "Default")
      (node (ref "U3") (pin "A7") (pinfunction "_DAT5m_A7") (pintype "passive"))
    )
    (net (code "70") (name "SD3_DATA6") (class "Default")
      (node (ref "U3") (pin "A12") (pinfunction "_DAT6m_A12") (pintype "passive"))
    )
    (net (code "71") (name "SD3_DATA7") (class "Default")
      (node (ref "U3") (pin "A14") (pinfunction "_DAT7m_A14") (pintype "passive"))
    )
    (net (code "72") (name "SD3_STROBE") (class "Default")
      (node (ref "DSm") (pin "1") (pinfunction "Pin1_1") (pintype "passive"))
      (node (ref "U3") (pin "B15") (pinfunction "_DSm_B15") (pintype "passive"))
    )
    (net (code "73") (name "VDD_ARM") (class "Default")
      (node (ref "C35") (pin "1") (pinfunction "1_1") (pintype "passive"))
      (node (ref "C36") (pin "1") (pinfunction "1_1") (pintype "passive"))
      (node (ref "C37") (pin "1") (pinfunction "1_1") (pintype "passive"))
      (node (ref "C38") (pin "1") (pinfunction "1_1") (pintype "passive"))
      (node (ref "C39") (pin "1") (pinfunction "1_1") (pintype "passive"))
      (node (ref "C40") (pin "1") (pinfunction "1_1") (pintype "passive"))
      (node (ref "C41") (pin "1") (pinfunction "1_1") (pintype "passive"))
      (node (ref "C42") (pin "1") (pinfunction "1_1") (pintype "passive"))
      (node (ref "C43") (pin "1") (pinfunction "1_1") (pintype "passive"))
      (node (ref "R1") (pin "1") (pinfunction "1_1") (pintype "passive"))
      (node (ref "R2") (pin "1") (pinfunction "1_1") (pintype "passive"))
      (node (ref "U3") (pin "AA16") (pinfunction "_VDDQ_AA16") (pintype "power_in"))
      (node (ref "U3") (pin "AA3") (pinfunction "_VDDQ_AA3") (pintype "power_in"))
      (node (ref "U3") (pin "L18") (pinfunction "VDDQ_L18") (pintype "power_in"))
      (node (ref "U3") (pin "L2") (pinfunction "VDDQ_L2") (pintype "power_in"))
      (node (ref "U3") (pin "T18") (pinfunction "VDDQ_T18") (pintype "power_in"))
      (node (ref "U3") (pin "T2") (pinfunction "_VDDQ_T2") (pintype "power_in"))
      (node (ref "U3") (pin "V18") (pinfunction "VDDQ_V18") (pintype "power_in"))
      (node (ref "U3") (pin "V2") (pinfunction "_VDDQ_V2") (pintype "power_in"))
    )
    (net (code "74") (name "unconnected-(U1A-DRAM_AC03{slash}CS1_A_{slash}_C0_{slash}_---PadP2)") (class "Default")
      (node (ref "U1") (pin "P2") (pinfunction "DRAM_AC03/CS1_A_/_C0_/_--_P2") (pintype "passive"))
    )
    (net (code "75") (name "unconnected-(U1A-DRAM_AC20{slash}CKE0_B_{slash}_CK_t_B_{slash}_CK_B-PadT1)") (class "Default")
      (node (ref "U1") (pin "T1") (pinfunction "DRAM_AC20/CKE0_B_/_CK_t_B_/_CK_B_T1") (pintype "passive"))
    )
    (net (code "76") (name "unconnected-(U1A-DRAM_AC21{slash}CKE1_B_{slash}_CK_c_B_{slash}_CK#_B-PadT2)") (class "Default")
      (node (ref "U1") (pin "T2") (pinfunction "DRAM_AC21/CKE1_B_/_CK_c_B_/_CK#_B_T2") (pintype "passive"))
    )
    (net (code "77") (name "unconnected-(U1A-DRAM_AC23{slash}CS0_B_{slash}_--_{slash}_---PadR4)") (class "Default")
      (node (ref "U1") (pin "R4") (pinfunction "DRAM_AC23/CS0_B_/_--_/_--_R4") (pintype "passive"))
    )
    (net (code "78") (name "unconnected-(U1A-DRAM_AC32{slash}CA4_B_{slash}_C2_{slash}_---PadR5)") (class "Default")
      (node (ref "U1") (pin "R5") (pinfunction "DRAM_AC32/CA4_B_/_C2_/_--_R5") (pintype "passive"))
    )
    (net (code "79") (name "unconnected-(U1A-DRAM_ALERT_N-PadN5)") (class "Default")
      (node (ref "U1") (pin "N5") (pinfunction "DRAM_ALERT_N_N5") (pintype "passive"))
    )
    (net (code "80") (name "unconnected-(U3A-_CS1_A-PadAA11)") (class "Default")
      (node (ref "U3") (pin "AA11") (pinfunction "_CS1_A_AA11") (pintype "passive"))
    )
    (net (code "81") (name "unconnected-(U3A-_ODT(ca)_A-PadAA14)") (class "Default")
      (node (ref "U3") (pin "AA14") (pinfunction "_ODT(ca)_A_AA14") (pintype "passive"))
    )
    (net (code "82") (name "unconnected-(U3A-_VSF1-PadD1)") (class "Default")
      (node (ref "U3") (pin "D1") (pinfunction "_VSF1_D1") (pintype "passive"))
    )
    (net (code "83") (name "unconnected-(U3A-_VSF2-PadE1)") (class "Default")
      (node (ref "U3") (pin "E1") (pinfunction "_VSF2_E1") (pintype "passive"))
    )
    (net (code "84") (name "unconnected-(U3A-_VSF3-PadD2)") (class "Default")
      (node (ref "U3") (pin "D2") (pinfunction "_VSF3_D2") (pintype "passive"))
    )
    (net (code "85") (name "unconnected-(U3C-NC-PadA19)") (class "Default")
      (node (ref "U3") (pin "A19") (pinfunction "NC_A19") (pintype "passive"))
    )
    (net (code "86") (name "unconnected-(U3C-NC-PadAA19)") (class "Default")
      (node (ref "U3") (pin "AA19") (pinfunction "NC_AA19") (pintype "passive"))
    )
    (net (code "87") (name "unconnected-(U3C-NC-PadD18)") (class "Default")
      (node (ref "U3") (pin "D18") (pinfunction "NC_D18") (pintype "passive"))
    )
    (net (code "88") (name "unconnected-(U3C-NC-PadD19)") (class "Default")
      (node (ref "U3") (pin "D19") (pinfunction "NC_D19") (pintype "passive"))
    )
    (net (code "89") (name "unconnected-(U3C-NC-PadE2)") (class "Default")
      (node (ref "U3") (pin "E2") (pinfunction "NC_E2") (pintype "passive"))
    )
    (net (code "90") (name "unconnected-(U3C-NC-PadE18)") (class "Default")
      (node (ref "U3") (pin "E18") (pinfunction "NC_E18") (pintype "passive"))
    )
    (net (code "91") (name "unconnected-(U3C-NC-PadE19)") (class "Default")
      (node (ref "U3") (pin "E19") (pinfunction "NC_E19") (pintype "passive"))
    )
    (net (code "92") (name "unconnected-(U3C-NC-PadF18)") (class "Default")
      (node (ref "U3") (pin "F18") (pinfunction "NC_F18") (pintype "passive"))
    )
    (net (code "93") (name "unconnected-(U3C-NC-PadF19)") (class "Default")
      (node (ref "U3") (pin "F19") (pinfunction "NC_F19") (pintype "passive"))
    )
    (net (code "94") (name "unconnected-(U3C-NC-PadG18)") (class "Default")
      (node (ref "U3") (pin "G18") (pinfunction "NC_G18") (pintype "passive"))
    )
    (net (code "95") (name "unconnected-(U3C-NC-PadG19)") (class "Default")
      (node (ref "U3") (pin "G19") (pinfunction "NC_G19") (pintype "passive"))
    )
    (net (code "96") (name "unconnected-(U3C-_NC-PadA1)") (class "Default")
      (node (ref "U3") (pin "A1") (pinfunction "_NC_A1") (pintype "passive"))
    )
    (net (code "97") (name "unconnected-(U3C-_NC-PadAA1)") (class "Default")
      (node (ref "U3") (pin "AA1") (pinfunction "_NC_AA1") (pintype "passive"))
    )
  )
)
